# ETH1G_RJ45MIDMNT.net
KiCad netlist of a schematic drawn in Altium Designer
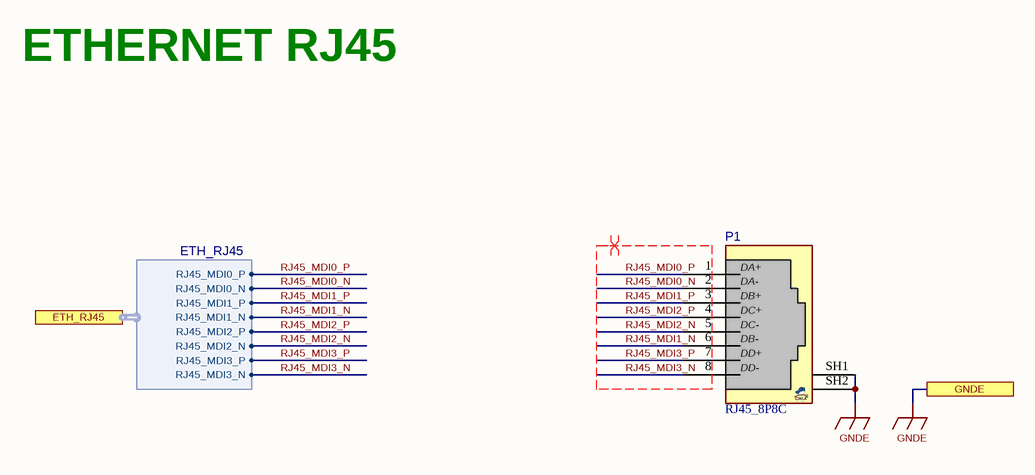
[diagram p0: ETH1G_RJ45MIDMNT.SchDoc]

(export (version "E")
  (design (tool "Eeschema 10.0.6"))
  (components
    (comp (ref "P1")
      (value "RJ45_8P8C")
      (footprint "RJ45_8S_RA_TD_SMD")
      (description "RJ45, 8P, SHIELDED, RightAngle, TabDown, SMDEMI panel ground")
      (fields (field (name "MANF") "Heling") (field (name "MANF_P#") "MJ88-B011-JRVS1-P"))
      (libsource (lib "conn_rj_ModularJack") (part "RJ45_8S_RA_TD_SMD"))
    )
  )
  (nets
    (net (code "2") (name "/RJ45_MDI0_N") (class "Default")
      (node (ref "P1") (pin "2") (pinfunction "DA-_2") (pintype "passive"))
    )
    (net (code "3") (name "/RJ45_MDI0_P") (class "Default")
      (node (ref "P1") (pin "1") (pinfunction "DA+_1") (pintype "passive"))
    )
    (net (code "4") (name "/RJ45_MDI1_N") (class "Default")
      (node (ref "P1") (pin "6") (pinfunction "DB-_6") (pintype "passive"))
    )
    (net (code "5") (name "/RJ45_MDI1_P") (class "Default")
      (node (ref "P1") (pin "3") (pinfunction "DB+_3") (pintype "passive"))
    )
    (net (code "6") (name "/RJ45_MDI2_N") (class "Default")
      (node (ref "P1") (pin "5") (pinfunction "DC-_5") (pintype "passive"))
    )
    (net (code "7") (name "/RJ45_MDI2_P") (class "Default")
      (node (ref "P1") (pin "4") (pinfunction "DC+_4") (pintype "passive"))
    )
    (net (code "8") (name "/RJ45_MDI3_N") (class "Default")
      (node (ref "P1") (pin "8") (pinfunction "DD-_8") (pintype "passive"))
    )
    (net (code "9") (name "/RJ45_MDI3_P") (class "Default")
      (node (ref "P1") (pin "7") (pinfunction "DD+_7") (pintype "passive"))
    )
    (net (code "11") (name "GNDE") (class "Default")
      (node (ref "P1") (pin "SH1") (pinfunction "SH1_SH1") (pintype "passive"))
      (node (ref "P1") (pin "SH2") (pinfunction "SH2_SH2") (pintype "passive"))
    )
  )
)
